# 01_USB_IO.net
KiCad netlist of a schematic drawn in Altium Designer
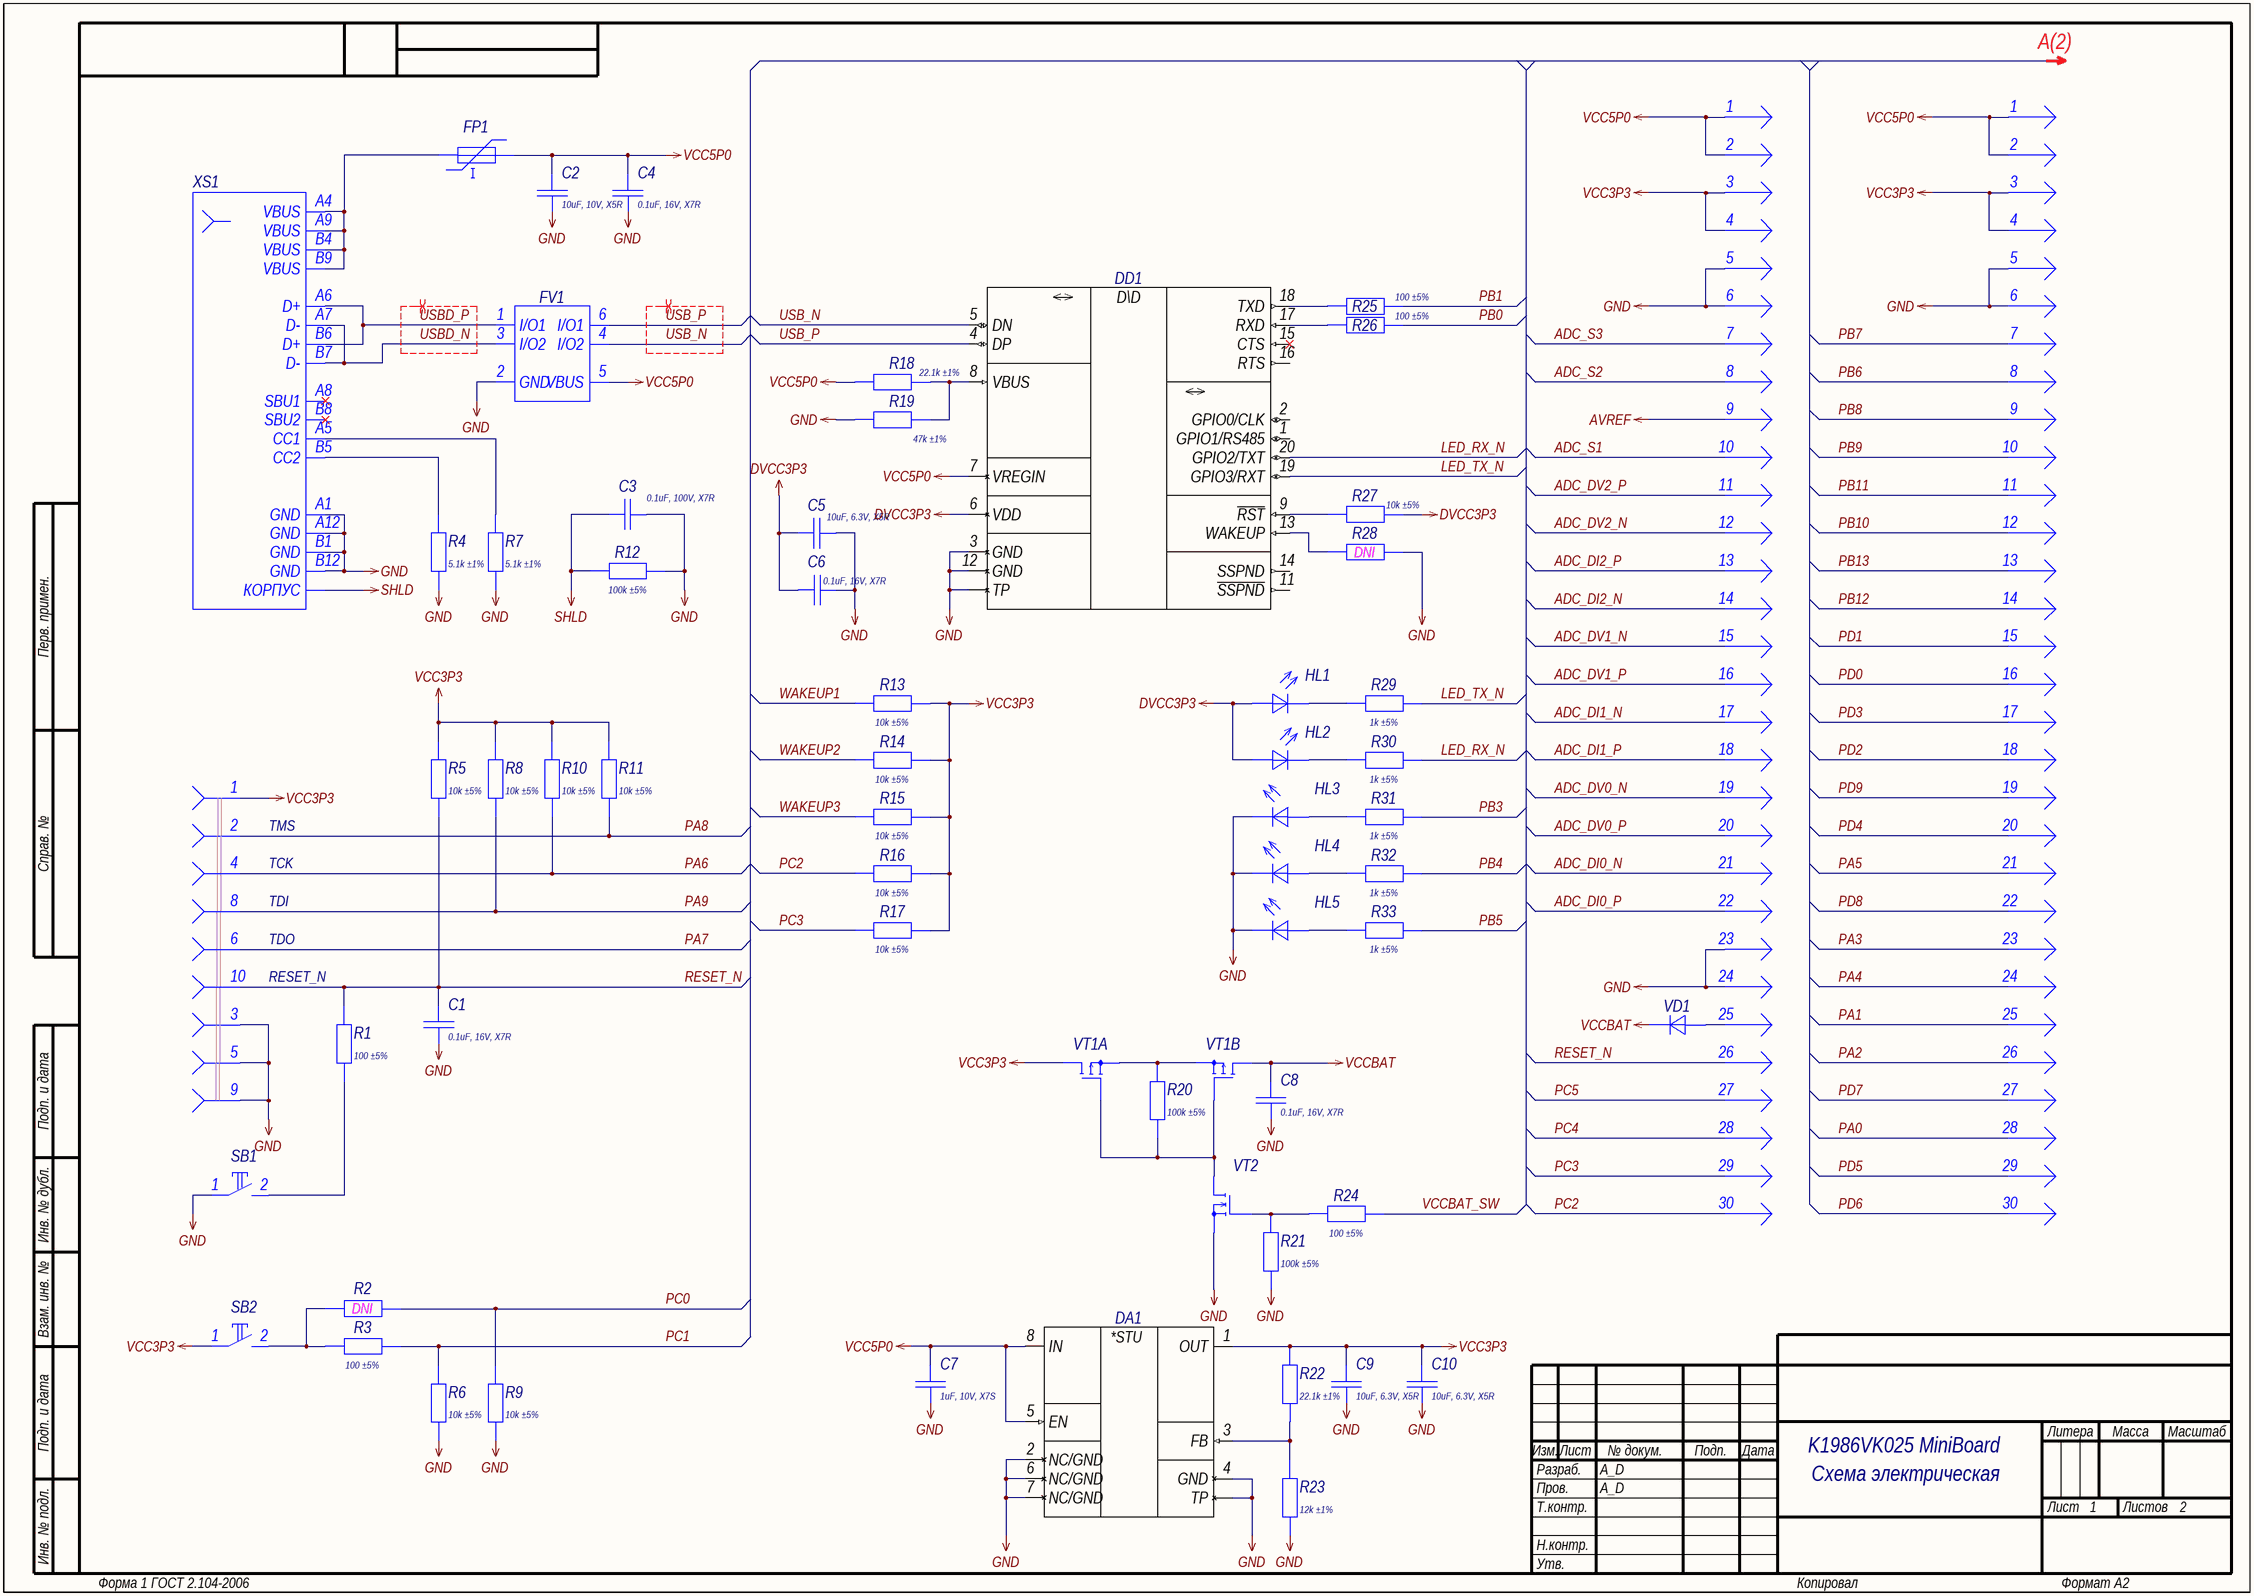
[diagram p0: 01_USB_IO.SchDoc]

(export (version "E")
  (design (tool "Eeschema 10.0.6"))
  (components
    (comp (ref "C1")
      (value "Capacitor")
      (footprint "C0402_100X050H050_H")
      (fields
        (field (name "SCHEMATIC VALUE") "0.1uF, 16V, X7R")
        (field (name "PART NUMBER") "GCM155R71C104KA55D")
        (field (name "VOLTAGE") "16V")
        (field (name "TOLERANCE") "±10%")
        (field (name "PUBLISHER") "Andrew Danich")
      )
      (libsource (lib "ADLib") (part "Capacitor"))
    )
    (comp (ref "C2")
      (value "Capacitor")
      (footprint "C0603_160X080H080_H")
      (fields
        (field (name "SCHEMATIC VALUE") "10uF, 10V, X5R")
        (field (name "PART NUMBER") "GRM188R61A106KE69D")
        (field (name "VOLTAGE") "10V")
        (field (name "TOLERANCE") "±10%")
        (field (name "PUBLISHER") "Andrew Danich")
      )
      (libsource (lib "ADLib") (part "Capacitor"))
    )
    (comp (ref "C3")
      (value "Capacitor")
      (footprint "C0603_160X080H080_H")
      (fields
        (field (name "SCHEMATIC VALUE") "0.1uF, 100V, X7R")
        (field (name "PART NUMBER") "GRM188R72A104KA35D")
        (field (name "VOLTAGE") "100V")
        (field (name "TOLERANCE") "±10%")
        (field (name "PUBLISHER") "Andrew Danich")
      )
      (libsource (lib "ADLib") (part "Capacitor"))
    )
    (comp (ref "C4")
      (value "Capacitor")
      (footprint "C0402_100X050H050_H")
      (fields
        (field (name "SCHEMATIC VALUE") "0.1uF, 16V, X7R")
        (field (name "PART NUMBER") "GCM155R71C104KA55D")
        (field (name "VOLTAGE") "16V")
        (field (name "TOLERANCE") "±10%")
        (field (name "PUBLISHER") "Andrew Danich")
      )
      (libsource (lib "ADLib") (part "Capacitor"))
    )
    (comp (ref "C5")
      (value "Capacitor")
      (footprint "C0402_100X050H050_H")
      (fields
        (field (name "SCHEMATIC VALUE") "10uF, 6.3V, X5R")
        (field (name "PART NUMBER") "GRM155R60J106ME15D")
        (field (name "VOLTAGE") "6.3V")
        (field (name "TOLERANCE") "±20%")
        (field (name "PUBLISHER") "Andrew Danich")
      )
      (libsource (lib "ADLib") (part "Capacitor"))
    )
    (comp (ref "C6")
      (value "Capacitor")
      (footprint "C0402_100X050H050_H")
      (fields
        (field (name "SCHEMATIC VALUE") "0.1uF, 16V, X7R")
        (field (name "PART NUMBER") "GCM155R71C104KA55D")
        (field (name "VOLTAGE") "16V")
        (field (name "TOLERANCE") "±10%")
        (field (name "PUBLISHER") "Andrew Danich")
      )
      (libsource (lib "ADLib") (part "Capacitor"))
    )
    (comp (ref "C7")
      (value "Capacitor")
      (footprint "C0402_100X050H050_H")
      (fields
        (field (name "SCHEMATIC VALUE") "1uF, 10V, X7S")
        (field (name "PART NUMBER") "GRM155C71A105KE11D")
        (field (name "VOLTAGE") "10V")
        (field (name "TOLERANCE") "±10%")
        (field (name "PUBLISHER") "Andrew Danich")
      )
      (libsource (lib "ADLib") (part "Capacitor"))
    )
    (comp (ref "C8")
      (value "Capacitor")
      (footprint "C0402_100X050H050_H")
      (fields
        (field (name "SCHEMATIC VALUE") "0.1uF, 16V, X7R")
        (field (name "PART NUMBER") "GCM155R71C104KA55D")
        (field (name "VOLTAGE") "16V")
        (field (name "TOLERANCE") "±10%")
        (field (name "PUBLISHER") "Andrew Danich")
      )
      (libsource (lib "ADLib") (part "Capacitor"))
    )
    (comp (ref "C9")
      (value "Capacitor")
      (footprint "C0402_100X050H050_H")
      (fields
        (field (name "SCHEMATIC VALUE") "10uF, 6.3V, X5R")
        (field (name "PART NUMBER") "GRM155R60J106ME15D")
        (field (name "VOLTAGE") "6.3V")
        (field (name "TOLERANCE") "±20%")
        (field (name "PUBLISHER") "Andrew Danich")
      )
      (libsource (lib "ADLib") (part "Capacitor"))
    )
    (comp (ref "C10")
      (value "Capacitor")
      (footprint "C0402_100X050H050_H")
      (fields
        (field (name "SCHEMATIC VALUE") "10uF, 6.3V, X5R")
        (field (name "PART NUMBER") "GRM155R60J106ME15D")
        (field (name "VOLTAGE") "6.3V")
        (field (name "TOLERANCE") "±20%")
        (field (name "PUBLISHER") "Andrew Danich")
      )
      (libsource (lib "ADLib") (part "Capacitor"))
    )
    (comp (ref "DA1")
      (value "TPS73501DRB")
      (footprint "VSON-8_065P300X300X100_N")
      (fields
        (field (name "PART NUMBER") "TPS73501DRBR")
        (field (name "MANUFACTURER") "Texas Instruments")
        (field (name "PUBLISHER") "Andrew Danich")
      )
      (libsource (lib "ADLib") (part "TPS73501DRB"))
    )
    (comp (ref "DD1")
      (value "CP2102N-xxx-GQFN20")
      (footprint "QFN-20_050P300X300X080_N")
      (fields
        (field (name "PART NUMBER") "CP2102N-A01-GQFN20")
        (field (name "MANUFACTURER") "Silicon Labs")
        (field (name "PUBLISHER") "Andrew Danich")
      )
      (libsource (lib "ADLib") (part "CP2102N-xxx-GQFN20"))
    )
    (comp (ref "FP1")
      (value "Fuse_PTC")
      (footprint "F0603_160X080H075_H")
      (fields (field (name "PART NUMBER") "0603L100SLYR") (field (name "MANUFACTURER") "Littelfuse"))
      (libsource (lib "ADLib") (part "Fuse_PTC"))
    )
    (comp (ref "FV1")
      (value "USBLC6-2x6")
      (footprint "SOT-666_050P160X120X060_N")
      (fields
        (field (name "PART NUMBER") "USBLC6-2P6")
        (field (name "MANUFACTURER") "STMicroelectronics")
        (field (name "PUBLISHER") "Andrew Danich")
      )
      (libsource (lib "ADLib") (part "USBLC6-2x6"))
    )
    (comp (ref "HL1")
      (value "TX")
      (footprint "LD0402")
      (fields
        (field (name "PART NUMBER") "KPHHS-1005SURCK")
        (field (name "MANUFACTURER") "Kingbright")
        (field (name "PUBLISHER") "Andrew Danich")
      )
      (libsource (lib "ADLib") (part "Led-1"))
    )
    (comp (ref "HL2")
      (value "RX")
      (footprint "LD0402")
      (fields
        (field (name "PART NUMBER") "KPHHS-1005CGCK")
        (field (name "MANUFACTURER") "Kingbright")
        (field (name "PUBLISHER") "Andrew Danich")
      )
      (libsource (lib "ADLib") (part "Led-1"))
    )
    (comp (ref "HL3")
      (value "PB3")
      (footprint "LD0402")
      (fields
        (field (name "PART NUMBER") "KPHHS-1005QBC-D-V")
        (field (name "MANUFACTURER") "Kingbright")
        (field (name "PUBLISHER") "Andrew Danich")
      )
      (libsource (lib "ADLib") (part "Led-1"))
    )
    (comp (ref "HL4")
      (value "PB4")
      (footprint "LD0402")
      (fields
        (field (name "PART NUMBER") "KPHHS-1005QBC-D-V")
        (field (name "MANUFACTURER") "Kingbright")
        (field (name "PUBLISHER") "Andrew Danich")
      )
      (libsource (lib "ADLib") (part "Led-1"))
    )
    (comp (ref "HL5")
      (value "PB5")
      (footprint "LD0402")
      (fields
        (field (name "PART NUMBER") "KPHHS-1005QBC-D-V")
        (field (name "MANUFACTURER") "Kingbright")
        (field (name "PUBLISHER") "Andrew Danich")
      )
      (libsource (lib "ADLib") (part "Led-1"))
    )
    (comp (ref "R1")
      (value "Resistor")
      (footprint "R0402_100X050H035_H")
      (fields
        (field (name "PART NUMBER") "RC0402JR-07100RL")
        (field (name "TOLERANCE") "±5%")
        (field (name "MANUFACTURER") "Yageo")
        (field (name "SCHEMATIC VALUE") "100 ±5%")
        (field (name "PUBLISHER") "Andrew Danich")
      )
      (libsource (lib "ADLib") (part "Resistor"))
    )
    (comp (ref "R2")
      (value "Resistor")
      (footprint "R0402_100X050H035_H")
      (fields
        (field (name "PART NUMBER") "RC0402JR-070RL")
        (field (name "TOLERANCE") "±5%")
        (field (name "MANUFACTURER") "Yageo")
        (field (name "PUBLISHER") "Andrew Danich")
      )
      (libsource (lib "ADLib") (part "Resistor"))
    )
    (comp (ref "R3")
      (value "Resistor")
      (footprint "R0402_100X050H035_H")
      (fields
        (field (name "PART NUMBER") "RC0402JR-07100RL")
        (field (name "TOLERANCE") "±5%")
        (field (name "MANUFACTURER") "Yageo")
        (field (name "SCHEMATIC VALUE") "100 ±5%")
        (field (name "PUBLISHER") "Andrew Danich")
      )
      (libsource (lib "ADLib") (part "Resistor"))
    )
    (comp (ref "R4")
      (value "Resistor")
      (footprint "R0402_100X050H035_H")
      (fields
        (field (name "PART NUMBER") "RC0402FR-075K1L")
        (field (name "TOLERANCE") "±1%")
        (field (name "MANUFACTURER") "Yageo")
        (field (name "SCHEMATIC VALUE") "5.1k ±1%")
        (field (name "PUBLISHER") "Andrew Danich")
      )
      (libsource (lib "ADLib") (part "Resistor"))
    )
    (comp (ref "R5")
      (value "Resistor")
      (footprint "R0402_100X050H035_H")
      (fields
        (field (name "PART NUMBER") "RC0402JR-0710KL")
        (field (name "TOLERANCE") "±5%")
        (field (name "MANUFACTURER") "Yageo")
        (field (name "SCHEMATIC VALUE") "10k ±5%")
        (field (name "PUBLISHER") "Andrew Danich")
      )
      (libsource (lib "ADLib") (part "Resistor"))
    )
    (comp (ref "R6")
      (value "Resistor")
      (footprint "R0402_100X050H035_H")
      (fields
        (field (name "PART NUMBER") "RC0402JR-0710KL")
        (field (name "TOLERANCE") "±5%")
        (field (name "MANUFACTURER") "Yageo")
        (field (name "SCHEMATIC VALUE") "10k ±5%")
        (field (name "PUBLISHER") "Andrew Danich")
      )
      (libsource (lib "ADLib") (part "Resistor"))
    )
    (comp (ref "R7")
      (value "Resistor")
      (footprint "R0402_100X050H035_H")
      (fields
        (field (name "PART NUMBER") "RC0402FR-075K1L")
        (field (name "TOLERANCE") "±1%")
        (field (name "MANUFACTURER") "Yageo")
        (field (name "SCHEMATIC VALUE") "5.1k ±1%")
        (field (name "PUBLISHER") "Andrew Danich")
      )
      (libsource (lib "ADLib") (part "Resistor"))
    )
    (comp (ref "R8")
      (value "Resistor")
      (footprint "R0402_100X050H035_H")
      (fields
        (field (name "PART NUMBER") "RC0402JR-0710KL")
        (field (name "TOLERANCE") "±5%")
        (field (name "MANUFACTURER") "Yageo")
        (field (name "SCHEMATIC VALUE") "10k ±5%")
        (field (name "PUBLISHER") "Andrew Danich")
      )
      (libsource (lib "ADLib") (part "Resistor"))
    )
    (comp (ref "R9")
      (value "Resistor")
      (footprint "R0402_100X050H035_H")
      (fields
        (field (name "PART NUMBER") "RC0402JR-0710KL")
        (field (name "TOLERANCE") "±5%")
        (field (name "MANUFACTURER") "Yageo")
        (field (name "SCHEMATIC VALUE") "10k ±5%")
        (field (name "PUBLISHER") "Andrew Danich")
      )
      (libsource (lib "ADLib") (part "Resistor"))
    )
    (comp (ref "R10")
      (value "Resistor")
      (footprint "R0402_100X050H035_H")
      (fields
        (field (name "PART NUMBER") "RC0402JR-0710KL")
        (field (name "TOLERANCE") "±5%")
        (field (name "MANUFACTURER") "Yageo")
        (field (name "SCHEMATIC VALUE") "10k ±5%")
        (field (name "PUBLISHER") "Andrew Danich")
      )
      (libsource (lib "ADLib") (part "Resistor"))
    )
    (comp (ref "R11")
      (value "Resistor")
      (footprint "R0402_100X050H035_H")
      (fields
        (field (name "PART NUMBER") "RC0402JR-0710KL")
        (field (name "TOLERANCE") "±5%")
        (field (name "MANUFACTURER") "Yageo")
        (field (name "SCHEMATIC VALUE") "10k ±5%")
        (field (name "PUBLISHER") "Andrew Danich")
      )
      (libsource (lib "ADLib") (part "Resistor"))
    )
    (comp (ref "R12")
      (value "Resistor")
      (footprint "R0402_100X050H035_H")
      (fields
        (field (name "PART NUMBER") "RC0402JR-07100KL")
        (field (name "TOLERANCE") "±5%")
        (field (name "MANUFACTURER") "Yageo")
        (field (name "SCHEMATIC VALUE") "100k ±5%")
        (field (name "PUBLISHER") "Andrew Danich")
      )
      (libsource (lib "ADLib") (part "Resistor"))
    )
    (comp (ref "R13")
      (value "Resistor")
      (footprint "R0402_100X050H035_H")
      (fields
        (field (name "PART NUMBER") "RC0402JR-0710KL")
        (field (name "TOLERANCE") "±5%")
        (field (name "MANUFACTURER") "Yageo")
        (field (name "SCHEMATIC VALUE") "10k ±5%")
        (field (name "PUBLISHER") "Andrew Danich")
      )
      (libsource (lib "ADLib") (part "Resistor"))
    )
    (comp (ref "R14")
      (value "Resistor")
      (footprint "R0402_100X050H035_H")
      (fields
        (field (name "PART NUMBER") "RC0402JR-0710KL")
        (field (name "TOLERANCE") "±5%")
        (field (name "MANUFACTURER") "Yageo")
        (field (name "SCHEMATIC VALUE") "10k ±5%")
        (field (name "PUBLISHER") "Andrew Danich")
      )
      (libsource (lib "ADLib") (part "Resistor"))
    )
    (comp (ref "R15")
      (value "Resistor")
      (footprint "R0402_100X050H035_H")
      (fields
        (field (name "PART NUMBER") "RC0402JR-0710KL")
        (field (name "TOLERANCE") "±5%")
        (field (name "MANUFACTURER") "Yageo")
        (field (name "SCHEMATIC VALUE") "10k ±5%")
        (field (name "PUBLISHER") "Andrew Danich")
      )
      (libsource (lib "ADLib") (part "Resistor"))
    )
    (comp (ref "R16")
      (value "Resistor")
      (footprint "R0402_100X050H035_H")
      (fields
        (field (name "PART NUMBER") "RC0402JR-0710KL")
        (field (name "TOLERANCE") "±5%")
        (field (name "MANUFACTURER") "Yageo")
        (field (name "SCHEMATIC VALUE") "10k ±5%")
        (field (name "PUBLISHER") "Andrew Danich")
      )
      (libsource (lib "ADLib") (part "Resistor"))
    )
    (comp (ref "R17")
      (value "Resistor")
      (footprint "R0402_100X050H035_H")
      (fields
        (field (name "PART NUMBER") "RC0402JR-0710KL")
        (field (name "TOLERANCE") "±5%")
        (field (name "MANUFACTURER") "Yageo")
        (field (name "SCHEMATIC VALUE") "10k ±5%")
        (field (name "PUBLISHER") "Andrew Danich")
      )
      (libsource (lib "ADLib") (part "Resistor"))
    )
    (comp (ref "R18")
      (value "Resistor")
      (footprint "R0402_100X050H035_H")
      (fields
        (field (name "SCHEMATIC VALUE") "22.1k ±1%")
        (field (name "PART NUMBER") "RC0402FR-0722K1L")
        (field (name "TOLERANCE") "±1%")
        (field (name "MANUFACTURER") "Yageo")
        (field (name "PUBLISHER") "Andrew Danich")
      )
      (libsource (lib "ADLib") (part "Resistor"))
    )
    (comp (ref "R19")
      (value "Resistor")
      (footprint "R0402_100X050H035_H")
      (fields
        (field (name "SCHEMATIC VALUE") "47k ±1%")
        (field (name "PART NUMBER") "RC0402FR-0747KL")
        (field (name "TOLERANCE") "±1%")
        (field (name "MANUFACTURER") "Yageo")
        (field (name "PUBLISHER") "Andrew Danich")
      )
      (libsource (lib "ADLib") (part "Resistor"))
    )
    (comp (ref "R20")
      (value "Resistor")
      (footprint "R0402_100X050H035_H")
      (fields
        (field (name "PART NUMBER") "RC0402JR-07100KL")
        (field (name "TOLERANCE") "±5%")
        (field (name "MANUFACTURER") "Yageo")
        (field (name "SCHEMATIC VALUE") "100k ±5%")
        (field (name "PUBLISHER") "Andrew Danich")
      )
      (libsource (lib "ADLib") (part "Resistor"))
    )
    (comp (ref "R21")
      (value "Resistor")
      (footprint "R0402_100X050H035_H")
      (fields
        (field (name "PART NUMBER") "RC0402JR-07100KL")
        (field (name "TOLERANCE") "±5%")
        (field (name "MANUFACTURER") "Yageo")
        (field (name "SCHEMATIC VALUE") "100k ±5%")
        (field (name "PUBLISHER") "Andrew Danich")
      )
      (libsource (lib "ADLib") (part "Resistor"))
    )
    (comp (ref "R22")
      (value "Resistor")
      (footprint "R0402_100X050H035_H")
      (fields
        (field (name "SCHEMATIC VALUE") "22.1k ±1%")
        (field (name "PART NUMBER") "RC0402FR-0722K1L")
        (field (name "TOLERANCE") "±1%")
        (field (name "MANUFACTURER") "Yageo")
        (field (name "PUBLISHER") "Andrew Danich")
      )
      (libsource (lib "ADLib") (part "Resistor"))
    )
    (comp (ref "R23")
      (value "Resistor")
      (footprint "R0402_100X050H035_H")
      (fields
        (field (name "SCHEMATIC VALUE") "12k ±1%")
        (field (name "PART NUMBER") "RC0402FR-0712KL")
        (field (name "TOLERANCE") "±1%")
        (field (name "MANUFACTURER") "Yageo")
        (field (name "PUBLISHER") "Andrew Danich")
      )
      (libsource (lib "ADLib") (part "Resistor"))
    )
    (comp (ref "R24")
      (value "Resistor")
      (footprint "R0402_100X050H035_H")
      (fields
        (field (name "PART NUMBER") "RC0402JR-07100RL")
        (field (name "TOLERANCE") "±5%")
        (field (name "MANUFACTURER") "Yageo")
        (field (name "SCHEMATIC VALUE") "100 ±5%")
        (field (name "PUBLISHER") "Andrew Danich")
      )
      (libsource (lib "ADLib") (part "Resistor"))
    )
    (comp (ref "R25")
      (value "Resistor")
      (footprint "R0402_100X050H035_H")
      (fields
        (field (name "PART NUMBER") "RC0402JR-07100RL")
        (field (name "TOLERANCE") "±5%")
        (field (name "MANUFACTURER") "Yageo")
        (field (name "SCHEMATIC VALUE") "100 ±5%")
        (field (name "PUBLISHER") "Andrew Danich")
      )
      (libsource (lib "ADLib") (part "Resistor"))
    )
    (comp (ref "R26")
      (value "Resistor")
      (footprint "R0402_100X050H035_H")
      (fields
        (field (name "PART NUMBER") "RC0402JR-07100RL")
        (field (name "TOLERANCE") "±5%")
        (field (name "MANUFACTURER") "Yageo")
        (field (name "SCHEMATIC VALUE") "100 ±5%")
        (field (name "PUBLISHER") "Andrew Danich")
      )
      (libsource (lib "ADLib") (part "Resistor"))
    )
    (comp (ref "R27")
      (value "Resistor")
      (footprint "R0402_100X050H035_H")
      (fields
        (field (name "PART NUMBER") "RC0402JR-0710KL")
        (field (name "TOLERANCE") "±5%")
        (field (name "MANUFACTURER") "Yageo")
        (field (name "SCHEMATIC VALUE") "10k ±5%")
        (field (name "PUBLISHER") "Andrew Danich")
      )
      (libsource (lib "ADLib") (part "Resistor"))
    )
    (comp (ref "R28")
      (value "Resistor")
      (footprint "R0402_100X050H035_H")
      (fields
        (field (name "PART NUMBER") "RC0402JR-0710KL")
        (field (name "TOLERANCE") "±5%")
        (field (name "MANUFACTURER") "Yageo")
        (field (name "PUBLISHER") "Andrew Danich")
      )
      (libsource (lib "ADLib") (part "Resistor"))
    )
    (comp (ref "R29")
      (value "Resistor")
      (footprint "R0402_100X050H035_H")
      (fields
        (field (name "SCHEMATIC VALUE") "1k ±5%")
        (field (name "PART NUMBER") "RC0402JR-071KL")
        (field (name "TOLERANCE") "±5%")
        (field (name "MANUFACTURER") "Yageo")
        (field (name "PUBLISHER") "Andrew Danich")
      )
      (libsource (lib "ADLib") (part "Resistor"))
    )
    (comp (ref "R30")
      (value "Resistor")
      (footprint "R0402_100X050H035_H")
      (fields
        (field (name "SCHEMATIC VALUE") "1k ±5%")
        (field (name "PART NUMBER") "RC0402JR-071KL")
        (field (name "TOLERANCE") "±5%")
        (field (name "MANUFACTURER") "Yageo")
        (field (name "PUBLISHER") "Andrew Danich")
      )
      (libsource (lib "ADLib") (part "Resistor"))
    )
    (comp (ref "R31")
      (value "Resistor")
      (footprint "R0402_100X050H035_H")
      (fields
        (field (name "SCHEMATIC VALUE") "1k ±5%")
        (field (name "PART NUMBER") "RC0402JR-071KL")
        (field (name "TOLERANCE") "±5%")
        (field (name "MANUFACTURER") "Yageo")
        (field (name "PUBLISHER") "Andrew Danich")
      )
      (libsource (lib "ADLib") (part "Resistor"))
    )
    (comp (ref "R32")
      (value "Resistor")
      (footprint "R0402_100X050H035_H")
      (fields
        (field (name "SCHEMATIC VALUE") "1k ±5%")
        (field (name "PART NUMBER") "RC0402JR-071KL")
        (field (name "TOLERANCE") "±5%")
        (field (name "MANUFACTURER") "Yageo")
        (field (name "PUBLISHER") "Andrew Danich")
      )
      (libsource (lib "ADLib") (part "Resistor"))
    )
    (comp (ref "R33")
      (value "Resistor")
      (footprint "R0402_100X050H035_H")
      (fields
        (field (name "SCHEMATIC VALUE") "1k ±5%")
        (field (name "PART NUMBER") "RC0402JR-071KL")
        (field (name "TOLERANCE") "±5%")
        (field (name "MANUFACTURER") "Yageo")
        (field (name "PUBLISHER") "Andrew Danich")
      )
      (libsource (lib "ADLib") (part "Resistor"))
    )
    (comp (ref "SB1")
      (value "Reset")
      (footprint "IT-1185AP")
      (fields (field (name "PART NUMBER") "IT-1185AP") (field (name "PUBLISHER") "Andrew Danich"))
      (libsource (lib "ADLib") (part "BT-01x-01p"))
    )
    (comp (ref "SB2")
      (value "Mode")
      (footprint "IT-1185AP")
      (fields (field (name "PART NUMBER") "IT-1185AP") (field (name "PUBLISHER") "Andrew Danich"))
      (libsource (lib "ADLib") (part "BT-01x-01p"))
    )
    (comp (ref "VD1")
      (value "Diode")
      (footprint "SOD-523")
      (fields
        (field (name "PART NUMBER") "1N4148WT-7")
        (field (name "MANUFACTURER") "Diodes Incorporated")
        (field (name "PUBLISHER") "Andrew Danich")
      )
      (libsource (lib "ADLib") (part "Diode"))
    )
    (comp (ref "VT1")
      (value "MOSFET-PP_8p_2")
      (footprint "SOT-1118-2M_065P200X200X065_N")
      (fields
        (field (name "PART NUMBER") "PMDPB70XP")
        (field (name "MANUFACTURER") "NXP Semiconductors")
        (field (name "PUBLISHER") "Andrew Danich")
      )
      (libsource (lib "") (part "MOSFET-PP_8p_2_1"))
    )
    (comp (ref "VT2")
      (value "MOSFET-N_32")
      (footprint "SOT-883B_035P060X100X040_N")
      (fields
        (field (name "PART NUMBER") "NX3008NBKMB")
        (field (name "MANUFACTURER") "NXP Semiconductors")
        (field (name "PUBLISHER") "Andrew Danich")
      )
      (libsource (lib "ADLib") (part "MOSFET-N_32"))
    )
    (comp (ref "XP1")
      (value "Text")
      (footprint "PLD-30")
      (fields (field (name "PART NUMBER") "PLD-30") (field (name "PUBLISHER") "Andrew Danich"))
      (libsource (lib "ADLib") (part "Con-30-M_S"))
    )
    (comp (ref "XP2")
      (value "Text")
      (footprint "PLD-30")
      (fields (field (name "PART NUMBER") "PLD-30") (field (name "PUBLISHER") "Andrew Danich"))
      (libsource (lib "ADLib") (part "Con-30-M_S"))
    )
    (comp (ref "XS1")
      (value "Text")
      (footprint "U262-161N-4BVC11")
      (fields
        (field (name "PART NUMBER") "U262-161N-4BVC11")
        (field (name "MANUFACTURER") "XKB Enterprise")
        (field (name "PUBLISHER") "Andrew Danich")
      )
      (libsource (lib "ADLib") (part "Con-USB_C-F-16P"))
    )
    (comp (ref "XS2")
      (value "JTAG-FFC")
      (footprint "XF2M-1015-1A")
      (fields
        (field (name "PART NUMBER") "XF2M-1015-1A")
        (field (name "MANUFACTURER") "Omron Electronics")
        (field (name "PUBLISHER") "Viktor Klishin")
      )
      (libsource (lib "ADLib") (part "Con-10-F_S"))
    )
  )
  (nets
    (net (code "1") (name "/ADC_DI0_N") (class "Default") (node (ref "XP1") (pin "21") (pintype "passive")))
    (net (code "2") (name "/ADC_DI0_P") (class "Default") (node (ref "XP1") (pin "22") (pintype "passive")))
    (net (code "3") (name "/ADC_DI1_N") (class "Default") (node (ref "XP1") (pin "17") (pintype "passive")))
    (net (code "4") (name "/ADC_DI1_P") (class "Default") (node (ref "XP1") (pin "18") (pintype "passive")))
    (net (code "5") (name "/ADC_DI2_N") (class "Default") (node (ref "XP1") (pin "14") (pintype "passive")))
    (net (code "6") (name "/ADC_DI2_P") (class "Default") (node (ref "XP1") (pin "13") (pintype "passive")))
    (net (code "7") (name "/ADC_DV0_N") (class "Default") (node (ref "XP1") (pin "19") (pintype "passive")))
    (net (code "8") (name "/ADC_DV0_P") (class "Default") (node (ref "XP1") (pin "20") (pintype "passive")))
    (net (code "9") (name "/ADC_DV1_N") (class "Default") (node (ref "XP1") (pin "15") (pintype "passive")))
    (net (code "10") (name "/ADC_DV1_P") (class "Default") (node (ref "XP1") (pin "16") (pintype "passive")))
    (net (code "11") (name "/ADC_DV2_N") (class "Default") (node (ref "XP1") (pin "12") (pintype "passive")))
    (net (code "12") (name "/ADC_DV2_P") (class "Default") (node (ref "XP1") (pin "11") (pintype "passive")))
    (net (code "13") (name "/ADC_S1") (class "Default") (node (ref "XP1") (pin "10") (pintype "passive")))
    (net (code "14") (name "/ADC_S2") (class "Default") (node (ref "XP1") (pin "8") (pintype "passive")))
    (net (code "15") (name "/ADC_S3") (class "Default") (node (ref "XP1") (pin "7") (pintype "passive")))
    (net (code "16") (name "/LED_RX_N") (class "Default")
      (node (ref "DD1") (pin "20") (pinfunction "GPIO2/TXT_20") (pintype "bidirectional"))
      (node (ref "R30") (pin "2") (pinfunction "2_2") (pintype "passive"))
    )
    (net (code "17") (name "/LED_TX_N") (class "Default")
      (node (ref "DD1") (pin "19") (pinfunction "GPIO3/RXT_19") (pintype "bidirectional"))
      (node (ref "R29") (pin "2") (pinfunction "2_2") (pintype "passive"))
    )
    (net (code "18") (name "/PA0") (class "Default") (node (ref "XP2") (pin "28") (pintype "passive")))
    (net (code "19") (name "/PA1") (class "Default") (node (ref "XP2") (pin "25") (pintype "passive")))
    (net (code "20") (name "/PA2") (class "Default") (node (ref "XP2") (pin "26") (pintype "passive")))
    (net (code "21") (name "/PA3") (class "Default") (node (ref "XP2") (pin "23") (pintype "passive")))
    (net (code "22") (name "/PA4") (class "Default") (node (ref "XP2") (pin "24") (pintype "passive")))
    (net (code "23") (name "/PA5") (class "Default") (node (ref "XP2") (pin "21") (pintype "passive")))
    (net (code "24") (name "/PA6") (class "Default")
      (node (ref "R10") (pin "1") (pinfunction "1_1") (pintype "passive"))
      (node (ref "XS2") (pin "4") (pintype "passive"))
    )
    (net (code "25") (name "/PA7") (class "Default") (node (ref "XS2") (pin "6") (pintype "passive")))
    (net (code "26") (name "/PA8") (class "Default")
      (node (ref "R11") (pin "1") (pinfunction "1_1") (pintype "passive"))
      (node (ref "XS2") (pin "2") (pintype "passive"))
    )
    (net (code "27") (name "/PA9") (class "Default")
      (node (ref "R8") (pin "1") (pinfunction "1_1") (pintype "passive"))
      (node (ref "XS2") (pin "8") (pintype "passive"))
    )
    (net (code "28") (name "/PB0") (class "Default")
      (node (ref "R26") (pin "1") (pinfunction "1_1") (pintype "passive"))
    )
    (net (code "29") (name "/PB1") (class "Default")
      (node (ref "R25") (pin "1") (pinfunction "1_1") (pintype "passive"))
    )
    (net (code "30") (name "/PB3") (class "Default")
      (node (ref "R31") (pin "2") (pinfunction "2_2") (pintype "passive"))
    )
    (net (code "31") (name "/PB4") (class "Default")
      (node (ref "R32") (pin "2") (pinfunction "2_2") (pintype "passive"))
    )
    (net (code "32") (name "/PB5") (class "Default")
      (node (ref "R33") (pin "2") (pinfunction "2_2") (pintype "passive"))
    )
    (net (code "33") (name "/PB6") (class "Default") (node (ref "XP2") (pin "8") (pintype "passive")))
    (net (code "34") (name "/PB7") (class "Default") (node (ref "XP2") (pin "7") (pintype "passive")))
    (net (code "35") (name "/PB8") (class "Default") (node (ref "XP2") (pin "9") (pintype "passive")))
    (net (code "36") (name "/PB9") (class "Default") (node (ref "XP2") (pin "10") (pintype "passive")))
    (net (code "37") (name "/PB10") (class "Default") (node (ref "XP2") (pin "12") (pintype "passive")))
    (net (code "38") (name "/PB11") (class "Default") (node (ref "XP2") (pin "11") (pintype "passive")))
    (net (code "39") (name "/PB12") (class "Default") (node (ref "XP2") (pin "14") (pintype "passive")))
    (net (code "40") (name "/PB13") (class "Default") (node (ref "XP2") (pin "13") (pintype "passive")))
    (net (code "41") (name "/PC0") (class "Default")
      (node (ref "R2") (pin "1") (pinfunction "1_1") (pintype "passive"))
      (node (ref "R9") (pin "2") (pinfunction "2_2") (pintype "passive"))
    )
    (net (code "42") (name "/PC1") (class "Default")
      (node (ref "R3") (pin "1") (pinfunction "1_1") (pintype "passive"))
      (node (ref "R6") (pin "2") (pinfunction "2_2") (pintype "passive"))
    )
    (net (code "43") (name "/PC2") (class "Default")
      (node (ref "R16") (pin "2") (pinfunction "2_2") (pintype "passive"))
      (node (ref "XP1") (pin "30") (pintype "passive"))
    )
    (net (code "44") (name "/PC3") (class "Default")
      (node (ref "R17") (pin "2") (pinfunction "2_2") (pintype "passive"))
      (node (ref "XP1") (pin "29") (pintype "passive"))
    )
    (net (code "45") (name "/PC4") (class "Default") (node (ref "XP1") (pin "28") (pintype "passive")))
    (net (code "46") (name "/PC5") (class "Default") (node (ref "XP1") (pin "27") (pintype "passive")))
    (net (code "47") (name "/PD0") (class "Default") (node (ref "XP2") (pin "16") (pintype "passive")))
    (net (code "48") (name "/PD1") (class "Default") (node (ref "XP2") (pin "15") (pintype "passive")))
    (net (code "49") (name "/PD2") (class "Default") (node (ref "XP2") (pin "18") (pintype "passive")))
    (net (code "50") (name "/PD3") (class "Default") (node (ref "XP2") (pin "17") (pintype "passive")))
    (net (code "51") (name "/PD4") (class "Default") (node (ref "XP2") (pin "20") (pintype "passive")))
    (net (code "52") (name "/PD5") (class "Default") (node (ref "XP2") (pin "29") (pintype "passive")))
    (net (code "53") (name "/PD6") (class "Default") (node (ref "XP2") (pin "30") (pintype "passive")))
    (net (code "54") (name "/PD7") (class "Default") (node (ref "XP2") (pin "27") (pintype "passive")))
    (net (code "55") (name "/PD8") (class "Default") (node (ref "XP2") (pin "22") (pintype "passive")))
    (net (code "56") (name "/PD9") (class "Default") (node (ref "XP2") (pin "19") (pintype "passive")))
    (net (code "57") (name "/RESET_N") (class "Default")
      (node (ref "C1") (pin "1") (pinfunction "1_1") (pintype "passive"))
      (node (ref "R1") (pin "2") (pinfunction "2_2") (pintype "passive"))
      (node (ref "R5") (pin "1") (pinfunction "1_1") (pintype "passive"))
      (node (ref "XP1") (pin "26") (pintype "passive"))
      (node (ref "XS2") (pin "10") (pintype "passive"))
    )
    (net (code "58") (name "/USBD_N") (class "Default")
      (node (ref "FV1") (pin "3") (pinfunction "I/O2_3") (pintype "passive"))
      (node (ref "XS1") (pin "A7") (pinfunction "D-_A7") (pintype "passive"))
      (node (ref "XS1") (pin "B7") (pinfunction "D-_B7") (pintype "passive"))
    )
    (net (code "59") (name "/USBD_P") (class "Default")
      (node (ref "FV1") (pin "1") (pinfunction "I/O1_1") (pintype "passive"))
      (node (ref "XS1") (pin "A6") (pinfunction "D+_A6") (pintype "passive"))
      (node (ref "XS1") (pin "B6") (pinfunction "D+_B6") (pintype "passive"))
    )
    (net (code "60") (name "/USB_N") (class "Default")
      (node (ref "DD1") (pin "5") (pinfunction "DN_5") (pintype "bidirectional"))
      (node (ref "FV1") (pin "4") (pinfunction "I/O2_4") (pintype "passive"))
    )
    (net (code "61") (name "/USB_P") (class "Default")
      (node (ref "DD1") (pin "4") (pinfunction "DP_4") (pintype "bidirectional"))
      (node (ref "FV1") (pin "6") (pinfunction "I/O1_6") (pintype "passive"))
    )
    (net (code "62") (name "/VCCBAT_SW") (class "Default")
      (node (ref "R24") (pin "1") (pinfunction "1_1") (pintype "passive"))
    )
    (net (code "63") (name "/WAKEUP1") (class "Default")
      (node (ref "R13") (pin "2") (pinfunction "2_2") (pintype "passive"))
    )
    (net (code "64") (name "/WAKEUP2") (class "Default")
      (node (ref "R14") (pin "2") (pinfunction "2_2") (pintype "passive"))
    )
    (net (code "65") (name "/WAKEUP3") (class "Default")
      (node (ref "R15") (pin "2") (pinfunction "2_2") (pintype "passive"))
    )
    (net (code "66") (name "AVREF") (class "Default") (node (ref "XP1") (pin "9") (pintype "passive")))
    (net (code "67") (name "DVCC3P3") (class "Default")
      (node (ref "C5") (pin "2") (pinfunction "2_2") (pintype "passive"))
      (node (ref "C6") (pin "1") (pinfunction "1_1") (pintype "passive"))
      (node (ref "DD1") (pin "6") (pinfunction "VDD_6") (pintype "power_in"))
      (node (ref "HL1") (pin "1") (pinfunction "А_1") (pintype "passive"))
      (node (ref "HL2") (pin "1") (pinfunction "А_1") (pintype "passive"))
      (node (ref "R27") (pin "1") (pinfunction "1_1") (pintype "passive"))
    )
    (net (code "68") (name "GND") (class "Default")
      (node (ref "C1") (pin "2") (pinfunction "2_2") (pintype "passive"))
      (node (ref "C10") (pin "1") (pinfunction "1_1") (pintype "passive"))
      (node (ref "C2") (pin "1") (pinfunction "1_1") (pintype "passive"))
      (node (ref "C3") (pin "1") (pinfunction "1_1") (pintype "passive"))
      (node (ref "C4") (pin "1") (pinfunction "1_1") (pintype "passive"))
      (node (ref "C5") (pin "1") (pinfunction "1_1") (pintype "passive"))
      (node (ref "C6") (pin "2") (pinfunction "2_2") (pintype "passive"))
      (node (ref "C7") (pin "1") (pinfunction "1_1") (pintype "passive"))
      (node (ref "C8") (pin "2") (pinfunction "2_2") (pintype "passive"))
      (node (ref "C9") (pin "1") (pinfunction "1_1") (pintype "passive"))
      (node (ref "DA1") (pin "2") (pinfunction "NC/GND_2") (pintype "passive"))
      (node (ref "DA1") (pin "4") (pinfunction "GND_4") (pintype "power_in"))
      (node (ref "DA1") (pin "6") (pinfunction "NC/GND_6") (pintype "passive"))
      (node (ref "DA1") (pin "7") (pinfunction "NC/GND_7") (pintype "passive"))
      (node (ref "DA1") (pin "TP") (pinfunction "TP_TP") (pintype "passive"))
      (node (ref "DD1") (pin "12") (pinfunction "GND_12") (pintype "power_in"))
      (node (ref "DD1") (pin "3") (pinfunction "GND_3") (pintype "power_in"))
      (node (ref "DD1") (pin "TP") (pinfunction "TP_TP") (pintype "power_in"))
      (node (ref "FV1") (pin "2") (pinfunction "GND_2") (pintype "passive"))
      (node (ref "HL3") (pin "2") (pinfunction "К_2") (pintype "passive"))
      (node (ref "HL4") (pin "2") (pinfunction "К_2") (pintype "passive"))
      (node (ref "HL5") (pin "2") (pinfunction "К_2") (pintype "passive"))
      (node (ref "R12") (pin "1") (pinfunction "1_1") (pintype "passive"))
      (node (ref "R19") (pin "2") (pinfunction "2_2") (pintype "passive"))
      (node (ref "R21") (pin "1") (pinfunction "1_1") (pintype "passive"))
      (node (ref "R23") (pin "1") (pinfunction "1_1") (pintype "passive"))
      (node (ref "R28") (pin "1") (pinfunction "1_1") (pintype "passive"))
      (node (ref "R4") (pin "1") (pinfunction "1_1") (pintype "passive"))
      (node (ref "R6") (pin "1") (pinfunction "1_1") (pintype "passive"))
      (node (ref "R7") (pin "1") (pinfunction "1_1") (pintype "passive"))
      (node (ref "R9") (pin "1") (pinfunction "1_1") (pintype "passive"))
      (node (ref "SB1") (pin "1") (pintype "passive"))
      (node (ref "VT2") (pin "2") (pinfunction "S_2") (pintype "passive"))
      (node (ref "XP1") (pin "23") (pintype "passive"))
      (node (ref "XP1") (pin "24") (pintype "passive"))
      (node (ref "XP1") (pin "5") (pintype "passive"))
      (node (ref "XP1") (pin "6") (pintype "passive"))
      (node (ref "XP2") (pin "5") (pintype "passive"))
      (node (ref "XP2") (pin "6") (pintype "passive"))
      (node (ref "XS1") (pin "A1") (pinfunction "GND_A1") (pintype "passive"))
      (node (ref "XS1") (pin "A12") (pinfunction "GND_A12") (pintype "passive"))
      (node (ref "XS1") (pin "B1") (pinfunction "GND_B1") (pintype "passive"))
      (node (ref "XS1") (pin "B12") (pinfunction "GND_B12") (pintype "passive"))
      (node (ref "XS2") (pin "3") (pintype "passive"))
      (node (ref "XS2") (pin "5") (pintype "passive"))
      (node (ref "XS2") (pin "9") (pintype "passive"))
    )
    (net (code "69") (name "Net-(DA1-FB)") (class "Default")
      (node (ref "DA1") (pin "3") (pinfunction "FB_3") (pintype "input"))
      (node (ref "R22") (pin "1") (pinfunction "1_1") (pintype "passive"))
      (node (ref "R23") (pin "2") (pinfunction "2_2") (pintype "passive"))
    )
    (net (code "70") (name "Net-(DD1-RXD)") (class "Default")
      (node (ref "DD1") (pin "17") (pinfunction "RXD_17") (pintype "input"))
      (node (ref "R26") (pin "2") (pinfunction "2_2") (pintype "passive"))
    )
    (net (code "71") (name "Net-(DD1-TXD)") (class "Default")
      (node (ref "DD1") (pin "18") (pinfunction "TXD_18") (pintype "output"))
      (node (ref "R25") (pin "2") (pinfunction "2_2") (pintype "passive"))
    )
    (net (code "72") (name "Net-(DD1-VBUS)") (class "Default")
      (node (ref "DD1") (pin "8") (pinfunction "VBUS_8") (pintype "input"))
      (node (ref "R18") (pin "1") (pinfunction "1_1") (pintype "passive"))
      (node (ref "R19") (pin "1") (pinfunction "1_1") (pintype "passive"))
    )
    (net (code "73") (name "Net-(DD1-WAKEUP)") (class "Default")
      (node (ref "DD1") (pin "13") (pinfunction "WAKEUP_13") (pintype "input"))
      (node (ref "R28") (pin "2") (pinfunction "2_2") (pintype "passive"))
    )
    (net (code "74") (name "Net-(DD1-~{RST})") (class "Default")
      (node (ref "DD1") (pin "9") (pinfunction "~{RST}_9") (pintype "input"))
      (node (ref "R27") (pin "2") (pinfunction "2_2") (pintype "passive"))
    )
    (net (code "75") (name "Net-(FP1-Pad1)") (class "Default")
      (node (ref "FP1") (pin "1") (pinfunction "1_1") (pintype "passive"))
      (node (ref "XS1") (pin "A4") (pinfunction "VBUS_A4") (pintype "passive"))
      (node (ref "XS1") (pin "A9") (pinfunction "VBUS_A9") (pintype "passive"))
      (node (ref "XS1") (pin "B4") (pinfunction "VBUS_B4") (pintype "passive"))
      (node (ref "XS1") (pin "B9") (pinfunction "VBUS_B9") (pintype "passive"))
    )
    (net (code "76") (name "Net-(HL1-К)") (class "Default")
      (node (ref "HL1") (pin "2") (pinfunction "К_2") (pintype "passive"))
      (node (ref "R29") (pin "1") (pinfunction "1_1") (pintype "passive"))
    )
    (net (code "77") (name "Net-(HL2-К)") (class "Default")
      (node (ref "HL2") (pin "2") (pinfunction "К_2") (pintype "passive"))
      (node (ref "R30") (pin "1") (pinfunction "1_1") (pintype "passive"))
    )
    (net (code "78") (name "Net-(HL3-А)") (class "Default")
      (node (ref "HL3") (pin "1") (pinfunction "А_1") (pintype "passive"))
      (node (ref "R31") (pin "1") (pinfunction "1_1") (pintype "passive"))
    )
    (net (code "79") (name "Net-(HL4-А)") (class "Default")
      (node (ref "HL4") (pin "1") (pinfunction "А_1") (pintype "passive"))
      (node (ref "R32") (pin "1") (pinfunction "1_1") (pintype "passive"))
    )
    (net (code "80") (name "Net-(HL5-А)") (class "Default")
      (node (ref "HL5") (pin "1") (pinfunction "А_1") (pintype "passive"))
      (node (ref "R33") (pin "1") (pinfunction "1_1") (pintype "passive"))
    )
    (net (code "81") (name "Net-(R1-Pad1)") (class "Default")
      (node (ref "R1") (pin "1") (pinfunction "1_1") (pintype "passive"))
      (node (ref "SB1") (pin "2") (pintype "passive"))
    )
    (net (code "82") (name "Net-(R2-Pad2)") (class "Default")
      (node (ref "R2") (pin "2") (pinfunction "2_2") (pintype "passive"))
      (node (ref "R3") (pin "2") (pinfunction "2_2") (pintype "passive"))
      (node (ref "SB2") (pin "2") (pintype "passive"))
    )
    (net (code "83") (name "Net-(VD1-А)") (class "Default")
      (node (ref "VD1") (pin "1") (pinfunction "А_1") (pintype "passive"))
      (node (ref "XP1") (pin "25") (pintype "passive"))
    )
    (net (code "84") (name "Net-(VT1A-G1)") (class "Default")
      (node (ref "R20") (pin "1") (pinfunction "1_1") (pintype "passive"))
      (node (ref "VT1") (pin "2") (pinfunction "G1_2") (pintype "passive"))
      (node (ref "VT1") (pin "5") (pinfunction "G2_5") (pintype "passive"))
      (node (ref "VT2") (pin "3") (pinfunction "D_3") (pintype "passive"))
    )
    (net (code "85") (name "Net-(VT1A-S1)") (class "Default")
      (node (ref "R20") (pin "2") (pinfunction "2_2") (pintype "passive"))
      (node (ref "VT1") (pin "1") (pinfunction "S1_1") (pintype "passive"))
      (node (ref "VT1") (pin "4") (pinfunction "S2_4") (pintype "passive"))
    )
    (net (code "86") (name "Net-(VT2-G)") (class "Default")
      (node (ref "R21") (pin "2") (pinfunction "2_2") (pintype "passive"))
      (node (ref "R24") (pin "2") (pinfunction "2_2") (pintype "passive"))
      (node (ref "VT2") (pin "1") (pinfunction "G_1") (pintype "passive"))
    )
    (net (code "87") (name "Net-(XS1-CC1)") (class "Default")
      (node (ref "R7") (pin "2") (pinfunction "2_2") (pintype "passive"))
      (node (ref "XS1") (pin "A5") (pinfunction "CC1_A5") (pintype "passive"))
    )
    (net (code "88") (name "Net-(XS1-CC2)") (class "Default")
      (node (ref "R4") (pin "2") (pinfunction "2_2") (pintype "passive"))
      (node (ref "XS1") (pin "B5") (pinfunction "CC2_B5") (pintype "passive"))
    )
    (net (code "89") (name "SHLD") (class "Default")
      (node (ref "C3") (pin "2") (pinfunction "2_2") (pintype "passive"))
      (node (ref "R12") (pin "2") (pinfunction "2_2") (pintype "passive"))
      (node (ref "XS1") (pin "SH") (pinfunction "КОРПУС_SH") (pintype "passive"))
    )
    (net (code "90") (name "VCC3P3") (class "Default")
      (node (ref "C10") (pin "2") (pinfunction "2_2") (pintype "passive"))
      (node (ref "C9") (pin "2") (pinfunction "2_2") (pintype "passive"))
      (node (ref "DA1") (pin "1") (pinfunction "OUT_1") (pintype "power_in"))
      (node (ref "R10") (pin "2") (pinfunction "2_2") (pintype "passive"))
      (node (ref "R11") (pin "2") (pinfunction "2_2") (pintype "passive"))
      (node (ref "R13") (pin "1") (pinfunction "1_1") (pintype "passive"))
      (node (ref "R14") (pin "1") (pinfunction "1_1") (pintype "passive"))
      (node (ref "R15") (pin "1") (pinfunction "1_1") (pintype "passive"))
      (node (ref "R16") (pin "1") (pinfunction "1_1") (pintype "passive"))
      (node (ref "R17") (pin "1") (pinfunction "1_1") (pintype "passive"))
      (node (ref "R22") (pin "2") (pinfunction "2_2") (pintype "passive"))
      (node (ref "R5") (pin "2") (pinfunction "2_2") (pintype "passive"))
      (node (ref "R8") (pin "2") (pinfunction "2_2") (pintype "passive"))
      (node (ref "SB2") (pin "1") (pintype "passive"))
      (node (ref "VT1") (pin "6") (pinfunction "D1_6") (pintype "passive"))
      (node (ref "XP1") (pin "3") (pintype "passive"))
      (node (ref "XP1") (pin "4") (pintype "passive"))
      (node (ref "XP2") (pin "3") (pintype "passive"))
      (node (ref "XP2") (pin "4") (pintype "passive"))
      (node (ref "XS2") (pin "1") (pintype "passive"))
    )
    (net (code "91") (name "VCC5P0") (class "Default")
      (node (ref "C2") (pin "2") (pinfunction "2_2") (pintype "passive"))
      (node (ref "C4") (pin "2") (pinfunction "2_2") (pintype "passive"))
      (node (ref "C7") (pin "2") (pinfunction "2_2") (pintype "passive"))
      (node (ref "DA1") (pin "5") (pinfunction "EN_5") (pintype "input"))
      (node (ref "DA1") (pin "8") (pinfunction "IN_8") (pintype "power_in"))
      (node (ref "DD1") (pin "7") (pinfunction "VREGIN_7") (pintype "power_in"))
      (node (ref "FP1") (pin "2") (pinfunction "2_2") (pintype "passive"))
      (node (ref "FV1") (pin "5") (pinfunction "VBUS_5") (pintype "passive"))
      (node (ref "R18") (pin "2") (pinfunction "2_2") (pintype "passive"))
      (node (ref "XP1") (pin "1") (pintype "passive"))
      (node (ref "XP1") (pin "2") (pintype "passive"))
      (node (ref "XP2") (pin "1") (pintype "passive"))
      (node (ref "XP2") (pin "2") (pintype "passive"))
    )
    (net (code "92") (name "VCCBAT") (class "Default")
      (node (ref "C8") (pin "1") (pinfunction "1_1") (pintype "passive"))
      (node (ref "VD1") (pin "2") (pinfunction "К_2") (pintype "passive"))
      (node (ref "VT1") (pin "3") (pinfunction "D2_3") (pintype "passive"))
    )
    (net (code "93") (name "unconnected-(DD1-CTS-Pad15)") (class "Default")
      (node (ref "DD1") (pin "15") (pinfunction "CTS_15") (pintype "input+no_connect"))
    )
    (net (code "94") (name "unconnected-(DD1-GPIO0{slash}CLK-Pad2)") (class "Default")
      (node (ref "DD1") (pin "2") (pinfunction "GPIO0/CLK_2") (pintype "bidirectional"))
    )
    (net (code "95") (name "unconnected-(DD1-GPIO1{slash}RS485-Pad1)") (class "Default")
      (node (ref "DD1") (pin "1") (pinfunction "GPIO1/RS485_1") (pintype "bidirectional"))
    )
    (net (code "96") (name "unconnected-(DD1-RTS-Pad16)") (class "Default")
      (node (ref "DD1") (pin "16") (pinfunction "RTS_16") (pintype "output"))
    )
    (net (code "97") (name "unconnected-(DD1-SSPND-Pad14)") (class "Default")
      (node (ref "DD1") (pin "14") (pinfunction "SSPND_14") (pintype "output"))
    )
    (net (code "98") (name "unconnected-(DD1-~{SSPND}-Pad11)") (class "Default")
      (node (ref "DD1") (pin "11") (pinfunction "~{SSPND}_11") (pintype "output"))
    )
    (net (code "99") (name "unconnected-(XS1-SBU1-PadA8)") (class "Default")
      (node (ref "XS1") (pin "A8") (pinfunction "SBU1_A8") (pintype "passive+no_connect"))
    )
    (net (code "100") (name "unconnected-(XS1-SBU2-PadB8)") (class "Default")
      (node (ref "XS1") (pin "B8") (pinfunction "SBU2_B8") (pintype "passive+no_connect"))
    )
  )
)
